# blinky.net
KiCad netlist of a schematic drawn in EAGLE
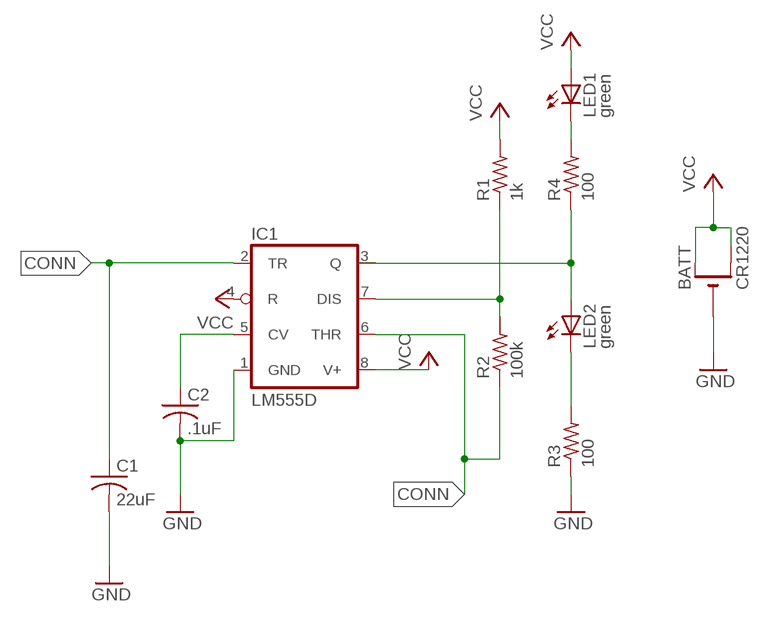
[diagram p0: schematic, sheet 1]

(export (version "E")
  (design (tool "Eeschema 10.0.6"))
  (components
    (comp (ref "BATT")
      (value "CR1220")
      (footprint "eagle-import:CR1220-SMD")
      (libsource (lib "eagle-import") (part "CR1220SMT"))
    )
    (comp (ref "C1")
      (value "22uF")
      (footprint "eagle-import:C0805")
      (libsource (lib "eagle-import") (part "C-USC0805"))
    )
    (comp (ref "C2")
      (value ".1uF")
      (footprint "eagle-import:C0805")
      (libsource (lib "eagle-import") (part "C-USC0805"))
    )
    (comp (ref "IC1")
      (value "LM555D")
      (footprint "eagle-import:SO08")
      (libsource (lib "eagle-import") (part "555DLM"))
    )
    (comp (ref "LED1")
      (value "green")
      (footprint "eagle-import:CHIPLED_0805")
      (libsource (lib "eagle-import") (part "LEDCHIPLED_0805"))
    )
    (comp (ref "LED2")
      (value "green")
      (footprint "eagle-import:CHIPLED_0805")
      (libsource (lib "eagle-import") (part "LEDCHIPLED_0805"))
    )
    (comp (ref "R1")
      (value "1k")
      (footprint "eagle-import:R0805")
      (libsource (lib "eagle-import") (part "R-US_R0805"))
    )
    (comp (ref "R2")
      (value "100k")
      (footprint "eagle-import:R0805")
      (libsource (lib "eagle-import") (part "R-US_R0805"))
    )
    (comp (ref "R3")
      (value "100")
      (footprint "eagle-import:R0805")
      (libsource (lib "eagle-import") (part "R-US_R0805"))
    )
    (comp (ref "R4")
      (value "100")
      (footprint "eagle-import:R0805")
      (libsource (lib "eagle-import") (part "R-US_R0805"))
    )
  )
  (nets
    (net (code "1") (name "CONN") (class "Default")
      (node (ref "C1") (pin "1") (pinfunction "1_1") (pintype "passive"))
      (node (ref "IC1") (pin "2") (pinfunction "TR_2") (pintype "input"))
      (node (ref "IC1") (pin "6") (pinfunction "THR_6") (pintype "input"))
      (node (ref "R2") (pin "1") (pinfunction "1_1") (pintype "passive"))
    )
    (net (code "2") (name "GND") (class "Default")
      (node (ref "BATT") (pin "-") (pinfunction "-_-") (pintype "passive"))
      (node (ref "C1") (pin "2") (pinfunction "2_2") (pintype "passive"))
      (node (ref "C2") (pin "2") (pinfunction "2_2") (pintype "passive"))
      (node (ref "IC1") (pin "1") (pinfunction "GND_1") (pintype "power_in"))
      (node (ref "R3") (pin "1") (pinfunction "1_1") (pintype "passive"))
    )
    (net (code "3") (name "Net-(IC1-CV)") (class "Default")
      (node (ref "C2") (pin "1") (pinfunction "1_1") (pintype "passive"))
      (node (ref "IC1") (pin "5") (pinfunction "CV_5") (pintype "input"))
    )
    (net (code "4") (name "Net-(IC1-DIS)") (class "Default")
      (node (ref "IC1") (pin "7") (pinfunction "DIS_7") (pintype "input"))
      (node (ref "R1") (pin "1") (pinfunction "1_1") (pintype "passive"))
    )
    (net (code "5") (name "Net-(LED1-PadC)") (class "Default")
      (node (ref "LED1") (pin "C") (pinfunction "C_C") (pintype "passive"))
      (node (ref "R4") (pin "2") (pinfunction "2_2") (pintype "passive"))
    )
    (net (code "6") (name "Net-(LED2-PadA)") (class "Default")
      (node (ref "LED2") (pin "A") (pinfunction "A_A") (pintype "passive"))
      (node (ref "R4") (pin "1") (pinfunction "1_1") (pintype "passive"))
    )
    (net (code "7") (name "Net-(LED2-PadC)") (class "Default")
      (node (ref "LED2") (pin "C") (pinfunction "C_C") (pintype "passive"))
      (node (ref "R3") (pin "2") (pinfunction "2_2") (pintype "passive"))
    )
    (net (code "8") (name "VCC") (class "Default")
      (node (ref "BATT") (pin "+$2") (pinfunction "+1_+$2") (pintype "passive"))
      (node (ref "IC1") (pin "4") (pinfunction "R_4") (pintype "input"))
      (node (ref "IC1") (pin "8") (pinfunction "V+_8") (pintype "power_in"))
      (node (ref "LED1") (pin "A") (pinfunction "A_A") (pintype "passive"))
      (node (ref "R1") (pin "2") (pinfunction "2_2") (pintype "passive"))
    )
    (net (code "9") (name "unconnected-(BATT-+-Pad+$1)") (class "Default")
      (node (ref "BATT") (pin "+$1") (pinfunction "+_+$1") (pintype "passive"))
    )
    (net (code "10") (name "unconnected-(IC1-Q-Pad3)") (class "Default")
      (node (ref "IC1") (pin "3") (pinfunction "Q_3") (pintype "output"))
    )
    (net (code "11") (name "unconnected-(R2-Pad2)") (class "Default")
      (node (ref "R2") (pin "2") (pinfunction "2_2") (pintype "passive"))
    )
  )
)
